# Grove_-_Button_v1_0.net
KiCad netlist of a schematic drawn in EAGLE
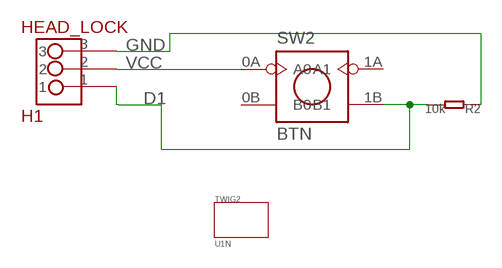
[diagram p0: schematic, sheet 1]

(export (version "E")
  (design (tool "Eeschema 10.0.6"))
  (components
    (comp (ref "H1")
      (value "HEAD_LOCK")
      (footprint "eagle-import:HEAD_LOCK")
      (libsource (lib "eagle-import") (part "HEAD_LOCK"))
    )
    (comp (ref "R2")
      (value "10k")
      (footprint "eagle-import:0603")
      (libsource (lib "eagle-import") (part "005-R0603"))
    )
    (comp (ref "SW2")
      (value "BTN")
      (footprint "eagle-import:BTN_8X8")
      (libsource (lib "eagle-import") (part "BTN"))
    )
    (comp (ref "TWIG2")
      (value "U1N")
      (footprint "eagle-import:U1N")
      (libsource (lib "eagle-import") (part "U1N"))
    )
  )
  (nets
    (net (code "1") (name "/D1") (class "Default")
      (node (ref "H1") (pin "1") (pinfunction "1_1") (pintype "passive"))
      (node (ref "R2") (pin "2") (pinfunction "2_2") (pintype "passive"))
      (node (ref "SW2") (pin "1B") (pinfunction "B1_1B") (pintype "bidirectional"))
    )
    (net (code "2") (name "/GND") (class "Default")
      (node (ref "H1") (pin "3") (pinfunction "3_3") (pintype "passive"))
      (node (ref "R2") (pin "1") (pinfunction "1_1") (pintype "passive"))
    )
    (net (code "3") (name "/VCC") (class "Default")
      (node (ref "H1") (pin "2") (pinfunction "2_2") (pintype "passive"))
      (node (ref "SW2") (pin "0A") (pinfunction "A0_0A") (pintype "bidirectional"))
    )
    (net (code "4") (name "unconnected-(SW2-A1-Pad1A)") (class "Default")
      (node (ref "SW2") (pin "1A") (pinfunction "A1_1A") (pintype "bidirectional"))
    )
    (net (code "5") (name "unconnected-(SW2-B0-Pad0B)") (class "Default")
      (node (ref "SW2") (pin "0B") (pinfunction "B0_0B") (pintype "bidirectional"))
    )
  )
)
